# PWR_Management_2026-06-21.net
KiCad netlist of a schematic drawn in Altium Designer
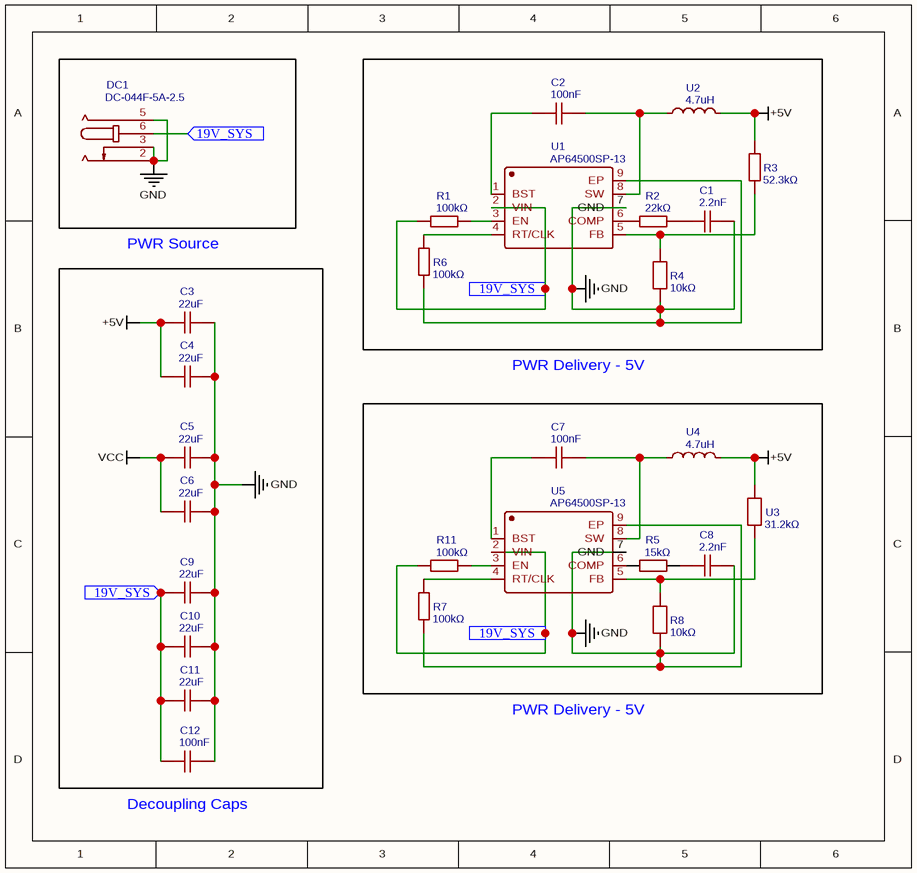
[diagram p0: PWR_Management_2026-06-21.schdoc]

(export (version "E")
  (design (tool "Eeschema 10.0.6"))
  (components
    (comp (ref "C1")
      (value "2.2nF")
      (fields
        (field (name "MANUFACTURER") "FOJAN(富捷)")
        (field (name "MANUFACTURER PART") "FCC0603B222K500CT")
        (field (name "CONTRIBUTOR") "lcsc")
      )
      (libsource (lib "altium-import") (part "root_0_2.2nF_"))
    )
    (comp (ref "C2")
      (value "100nF")
      (fields
        (field (name "MANUFACTURER") "muRata(村田)")
        (field (name "MANUFACTURER PART") "GRM188R71H104KA93D")
      )
      (libsource (lib "altium-import") (part "root_0_100nF_"))
    )
    (comp (ref "C3")
      (value "22uF")
      (fields
        (field (name "MANUFACTURER") "Chinocera(华瓷)")
        (field (name "MANUFACTURER PART") "HGC0603R5226M160NTHJ")
        (field (name "CONTRIBUTOR") "lcsc")
      )
      (libsource (lib "altium-import") (part "root_0_22uF_"))
    )
    (comp (ref "C4")
      (value "22uF")
      (fields
        (field (name "MANUFACTURER") "Chinocera(华瓷)")
        (field (name "MANUFACTURER PART") "HGC0603R5226M160NTHJ")
        (field (name "CONTRIBUTOR") "lcsc")
      )
      (libsource (lib "altium-import") (part "root_0_22uF_"))
    )
    (comp (ref "C5")
      (value "22uF")
      (fields
        (field (name "MANUFACTURER") "Chinocera(华瓷)")
        (field (name "MANUFACTURER PART") "HGC0603R5226M160NTHJ")
        (field (name "CONTRIBUTOR") "lcsc")
      )
      (libsource (lib "altium-import") (part "root_0_22uF_"))
    )
    (comp (ref "C6")
      (value "22uF")
      (fields
        (field (name "MANUFACTURER") "Chinocera(华瓷)")
        (field (name "MANUFACTURER PART") "HGC0603R5226M160NTHJ")
        (field (name "CONTRIBUTOR") "lcsc")
      )
      (libsource (lib "altium-import") (part "root_0_22uF_"))
    )
    (comp (ref "C7")
      (value "100nF")
      (fields
        (field (name "MANUFACTURER") "muRata(村田)")
        (field (name "MANUFACTURER PART") "GRM188R71H104KA93D")
      )
      (libsource (lib "altium-import") (part "root_0_100nF_"))
    )
    (comp (ref "C8")
      (value "2.2nF")
      (fields
        (field (name "MANUFACTURER") "FOJAN(富捷)")
        (field (name "MANUFACTURER PART") "FCC0603B222K500CT")
        (field (name "CONTRIBUTOR") "lcsc")
      )
      (libsource (lib "altium-import") (part "root_0_2.2nF_"))
    )
    (comp (ref "C9")
      (value "22uF")
      (fields
        (field (name "MANUFACTURER") "muRata(村田)")
        (field (name "MANUFACTURER PART") "KCM55QR71H226KH13K")
        (field (name "CONTRIBUTOR") "lcsc")
      )
      (libsource (lib "altium-import") (part "root_0_22uF_"))
    )
    (comp (ref "C10")
      (value "22uF")
      (fields
        (field (name "MANUFACTURER") "muRata(村田)")
        (field (name "MANUFACTURER PART") "KCM55QR71H226KH13K")
        (field (name "CONTRIBUTOR") "lcsc")
      )
      (libsource (lib "altium-import") (part "root_0_22uF_"))
    )
    (comp (ref "C11")
      (value "22uF")
      (fields
        (field (name "MANUFACTURER") "muRata(村田)")
        (field (name "MANUFACTURER PART") "KCM55QR71H226KH13K")
        (field (name "CONTRIBUTOR") "lcsc")
      )
      (libsource (lib "altium-import") (part "root_0_22uF_"))
    )
    (comp (ref "C12")
      (value "100nF")
      (fields
        (field (name "MANUFACTURER") "muRata(村田)")
        (field (name "MANUFACTURER PART") "GRM188R71H104KA93D")
      )
      (libsource (lib "altium-import") (part "root_0_100nF_"))
    )
    (comp (ref "DC1")
      (value "DC-044F-5A-2.5")
      (fields (field (name "MANUFACTURER") "XKB Connection(中国星坤)") (field (name "CONTRIBUTOR") "lcsc"))
      (libsource (lib "altium-import") (part "root_0_DC-044F-5A-2.5_"))
    )
    (comp (ref "R1")
      (value "100kΩ")
      (fields
        (field (name "MANUFACTURER") "FH(风华)")
        (field (name "MANUFACTURER PART") "RS-03K1003FT")
        (field (name "CONTRIBUTOR") "LCSC")
      )
      (libsource (lib "altium-import") (part "root_0_100kΩ_"))
    )
    (comp (ref "R2")
      (value "22kΩ")
      (fields
        (field (name "MANUFACTURER") "FH(风华)")
        (field (name "MANUFACTURER PART") "RS-03K2202FT")
        (field (name "CONTRIBUTOR") "LCSC")
      )
      (libsource (lib "altium-import") (part "root_0_22kΩ_"))
    )
    (comp (ref "R3")
      (value "52.3kΩ")
      (fields
        (field (name "MANUFACTURER") "FH(风华)")
        (field (name "MANUFACTURER PART") "RS-03K5232FT")
        (field (name "CONTRIBUTOR") "LCSC")
      )
      (libsource (lib "altium-import") (part "root_3_52.3kΩ_"))
    )
    (comp (ref "R4")
      (value "10kΩ")
      (fields
        (field (name "MANUFACTURER") "Viking(光颉)")
        (field (name "MANUFACTURER PART") "AR03BTS1002")
        (field (name "CONTRIBUTOR") "lcsc")
      )
      (libsource (lib "altium-import") (part "root_1_10kΩ_"))
    )
    (comp (ref "R5")
      (value "15kΩ")
      (fields (field (name "MANUFACTURER") "LIZ(丽智电子)") (field (name "MANUFACTURER PART") "CR0603FA1502G"))
      (libsource (lib "altium-import") (part "root_0_15kΩ_"))
    )
    (comp (ref "R6")
      (value "100kΩ")
      (fields
        (field (name "MANUFACTURER") "FH(风华)")
        (field (name "MANUFACTURER PART") "RS-03K1003FT")
        (field (name "CONTRIBUTOR") "LCSC")
      )
      (libsource (lib "altium-import") (part "root_1_100kΩ_"))
    )
    (comp (ref "R7")
      (value "100kΩ")
      (fields
        (field (name "MANUFACTURER") "FH(风华)")
        (field (name "MANUFACTURER PART") "RS-03K1003FT")
        (field (name "CONTRIBUTOR") "LCSC")
      )
      (libsource (lib "altium-import") (part "root_1_100kΩ_"))
    )
    (comp (ref "R8")
      (value "10kΩ")
      (fields
        (field (name "MANUFACTURER") "Viking(光颉)")
        (field (name "MANUFACTURER PART") "AR03BTS1002")
        (field (name "CONTRIBUTOR") "lcsc")
      )
      (libsource (lib "altium-import") (part "root_1_10kΩ_"))
    )
    (comp (ref "R11")
      (value "100kΩ")
      (fields
        (field (name "MANUFACTURER") "FH(风华)")
        (field (name "MANUFACTURER PART") "RS-03K1003FT")
        (field (name "CONTRIBUTOR") "LCSC")
      )
      (libsource (lib "altium-import") (part "root_0_100kΩ_"))
    )
    (comp (ref "U1")
      (value "AP64500SP-13")
      (fields (field (name "MANUFACTURER") "DIODES(美台)") (field (name "CONTRIBUTOR") "LCSC"))
      (libsource (lib "altium-import") (part "root_0_AP64500SP-13_"))
    )
    (comp (ref "U2")
      (value "4.7uH")
      (fields
        (field (name "MANUFACTURER") "APV(爱普微)")
        (field (name "MANUFACTURER PART") "APH0630T4R7M")
        (field (name "CONTRIBUTOR") "lcsc")
      )
      (libsource (lib "altium-import") (part "root_0_4.7uH_"))
    )
    (comp (ref "U3")
      (value "31.2kΩ")
      (fields
        (field (name "MANUFACTURER") "YAGEO(国巨)")
        (field (name "MANUFACTURER PART") "RT0603DRE0731K2L")
        (field (name "CONTRIBUTOR") "lcsc")
      )
      (libsource (lib "altium-import") (part "root_1_31.2kΩ_"))
    )
    (comp (ref "U4")
      (value "4.7uH")
      (fields
        (field (name "MANUFACTURER") "APV(爱普微)")
        (field (name "MANUFACTURER PART") "APH0630T4R7M")
        (field (name "CONTRIBUTOR") "lcsc")
      )
      (libsource (lib "altium-import") (part "root_0_4.7uH_"))
    )
    (comp (ref "U5")
      (value "AP64500SP-13")
      (fields (field (name "MANUFACTURER") "DIODES(美台)") (field (name "CONTRIBUTOR") "LCSC"))
      (libsource (lib "altium-import") (part "root_0_AP64500SP-13_"))
    )
  )
  (nets
    (net (code "1") (name "+5V") (class "Default")
      (node (ref "C3") (pin "1") (pinfunction "1_1") (pintype "passive"))
      (node (ref "C4") (pin "1") (pinfunction "1_1") (pintype "passive"))
      (node (ref "R3") (pin "1") (pinfunction "1_1") (pintype "passive"))
      (node (ref "U2") (pin "2") (pinfunction "2_2") (pintype "passive"))
      (node (ref "U3") (pin "2") (pinfunction "2_2") (pintype "passive"))
      (node (ref "U4") (pin "2") (pinfunction "2_2") (pintype "passive"))
    )
    (net (code "2") (name "/19V_SYS") (class "Default")
      (node (ref "C10") (pin "1") (pinfunction "1_1") (pintype "passive"))
      (node (ref "C11") (pin "1") (pinfunction "1_1") (pintype "passive"))
      (node (ref "C12") (pin "1") (pinfunction "1_1") (pintype "passive"))
      (node (ref "C9") (pin "1") (pinfunction "1_1") (pintype "passive"))
      (node (ref "DC1") (pin "6") (pinfunction "6_6") (pintype "passive"))
      (node (ref "R1") (pin "1") (pinfunction "1_1") (pintype "passive"))
      (node (ref "R11") (pin "1") (pinfunction "1_1") (pintype "passive"))
      (node (ref "U1") (pin "2") (pinfunction "VIN_2") (pintype "passive"))
      (node (ref "U5") (pin "2") (pinfunction "VIN_2") (pintype "passive"))
    )
    (net (code "3") (name "GND") (class "Default")
      (node (ref "C1") (pin "2") (pinfunction "2_2") (pintype "passive"))
      (node (ref "C10") (pin "2") (pinfunction "2_2") (pintype "passive"))
      (node (ref "C11") (pin "2") (pinfunction "2_2") (pintype "passive"))
      (node (ref "C12") (pin "2") (pinfunction "2_2") (pintype "passive"))
      (node (ref "C3") (pin "2") (pinfunction "2_2") (pintype "passive"))
      (node (ref "C4") (pin "2") (pinfunction "2_2") (pintype "passive"))
      (node (ref "C5") (pin "2") (pinfunction "2_2") (pintype "passive"))
      (node (ref "C6") (pin "2") (pinfunction "2_2") (pintype "passive"))
      (node (ref "C8") (pin "2") (pinfunction "2_2") (pintype "passive"))
      (node (ref "C9") (pin "2") (pinfunction "2_2") (pintype "passive"))
      (node (ref "DC1") (pin "2") (pinfunction "2_2") (pintype "passive"))
      (node (ref "DC1") (pin "3") (pinfunction "3_3") (pintype "passive"))
      (node (ref "DC1") (pin "5") (pinfunction "5_5") (pintype "passive"))
      (node (ref "R4") (pin "1") (pinfunction "1_1") (pintype "passive"))
      (node (ref "R6") (pin "1") (pinfunction "1_1") (pintype "passive"))
      (node (ref "R7") (pin "1") (pinfunction "1_1") (pintype "passive"))
      (node (ref "R8") (pin "1") (pinfunction "1_1") (pintype "passive"))
      (node (ref "U1") (pin "7") (pinfunction "GND_7") (pintype "passive"))
      (node (ref "U1") (pin "9") (pinfunction "EP_9") (pintype "passive"))
      (node (ref "U5") (pin "7") (pinfunction "GND_7") (pintype "passive"))
      (node (ref "U5") (pin "9") (pinfunction "EP_9") (pintype "passive"))
    )
    (net (code "4") (name "Net-(C1-Pad1)") (class "Default")
      (node (ref "C1") (pin "1") (pinfunction "1_1") (pintype "passive"))
      (node (ref "R2") (pin "2") (pinfunction "2_2") (pintype "passive"))
    )
    (net (code "5") (name "Net-(C8-Pad1)") (class "Default")
      (node (ref "C8") (pin "1") (pinfunction "1_1") (pintype "passive"))
      (node (ref "R5") (pin "2") (pinfunction "2_2") (pintype "passive"))
    )
    (net (code "6") (name "Net-(U1-BST)") (class "Default")
      (node (ref "C2") (pin "1") (pinfunction "1_1") (pintype "passive"))
      (node (ref "U1") (pin "1") (pinfunction "BST_1") (pintype "passive"))
    )
    (net (code "7") (name "Net-(U1-COMP)") (class "Default")
      (node (ref "R2") (pin "1") (pinfunction "1_1") (pintype "passive"))
      (node (ref "U1") (pin "6") (pinfunction "COMP_6") (pintype "passive"))
    )
    (net (code "8") (name "Net-(U1-EN)") (class "Default")
      (node (ref "R1") (pin "2") (pinfunction "2_2") (pintype "passive"))
      (node (ref "U1") (pin "3") (pinfunction "EN_3") (pintype "passive"))
    )
    (net (code "9") (name "Net-(U1-FB)") (class "Default")
      (node (ref "R3") (pin "2") (pinfunction "2_2") (pintype "passive"))
      (node (ref "R4") (pin "2") (pinfunction "2_2") (pintype "passive"))
      (node (ref "U1") (pin "5") (pinfunction "FB_5") (pintype "passive"))
    )
    (net (code "10") (name "Net-(U1-RT{slash}CLK)") (class "Default")
      (node (ref "R6") (pin "2") (pinfunction "2_2") (pintype "passive"))
      (node (ref "U1") (pin "4") (pinfunction "RT/CLK_4") (pintype "passive"))
    )
    (net (code "11") (name "Net-(U1-SW)") (class "Default")
      (node (ref "C2") (pin "2") (pinfunction "2_2") (pintype "passive"))
      (node (ref "U1") (pin "8") (pinfunction "SW_8") (pintype "passive"))
      (node (ref "U2") (pin "1") (pinfunction "1_1") (pintype "passive"))
    )
    (net (code "12") (name "Net-(U5-BST)") (class "Default")
      (node (ref "C7") (pin "1") (pinfunction "1_1") (pintype "passive"))
      (node (ref "U5") (pin "1") (pinfunction "BST_1") (pintype "passive"))
    )
    (net (code "13") (name "Net-(U5-COMP)") (class "Default")
      (node (ref "R5") (pin "1") (pinfunction "1_1") (pintype "passive"))
      (node (ref "U5") (pin "6") (pinfunction "COMP_6") (pintype "passive"))
    )
    (net (code "14") (name "Net-(U5-EN)") (class "Default")
      (node (ref "R11") (pin "2") (pinfunction "2_2") (pintype "passive"))
      (node (ref "U5") (pin "3") (pinfunction "EN_3") (pintype "passive"))
    )
    (net (code "15") (name "Net-(U5-FB)") (class "Default")
      (node (ref "R8") (pin "2") (pinfunction "2_2") (pintype "passive"))
      (node (ref "U3") (pin "1") (pinfunction "1_1") (pintype "passive"))
      (node (ref "U5") (pin "5") (pinfunction "FB_5") (pintype "passive"))
    )
    (net (code "16") (name "Net-(U5-RT{slash}CLK)") (class "Default")
      (node (ref "R7") (pin "2") (pinfunction "2_2") (pintype "passive"))
      (node (ref "U5") (pin "4") (pinfunction "RT/CLK_4") (pintype "passive"))
    )
    (net (code "17") (name "Net-(U5-SW)") (class "Default")
      (node (ref "C7") (pin "2") (pinfunction "2_2") (pintype "passive"))
      (node (ref "U4") (pin "1") (pinfunction "1_1") (pintype "passive"))
      (node (ref "U5") (pin "8") (pinfunction "SW_8") (pintype "passive"))
    )
    (net (code "18") (name "VCC") (class "Default")
      (node (ref "C5") (pin "1") (pinfunction "1_1") (pintype "passive"))
      (node (ref "C6") (pin "1") (pinfunction "1_1") (pintype "passive"))
    )
  )
)
